# POWER.net
KiCad netlist of a schematic drawn in Altium Designer
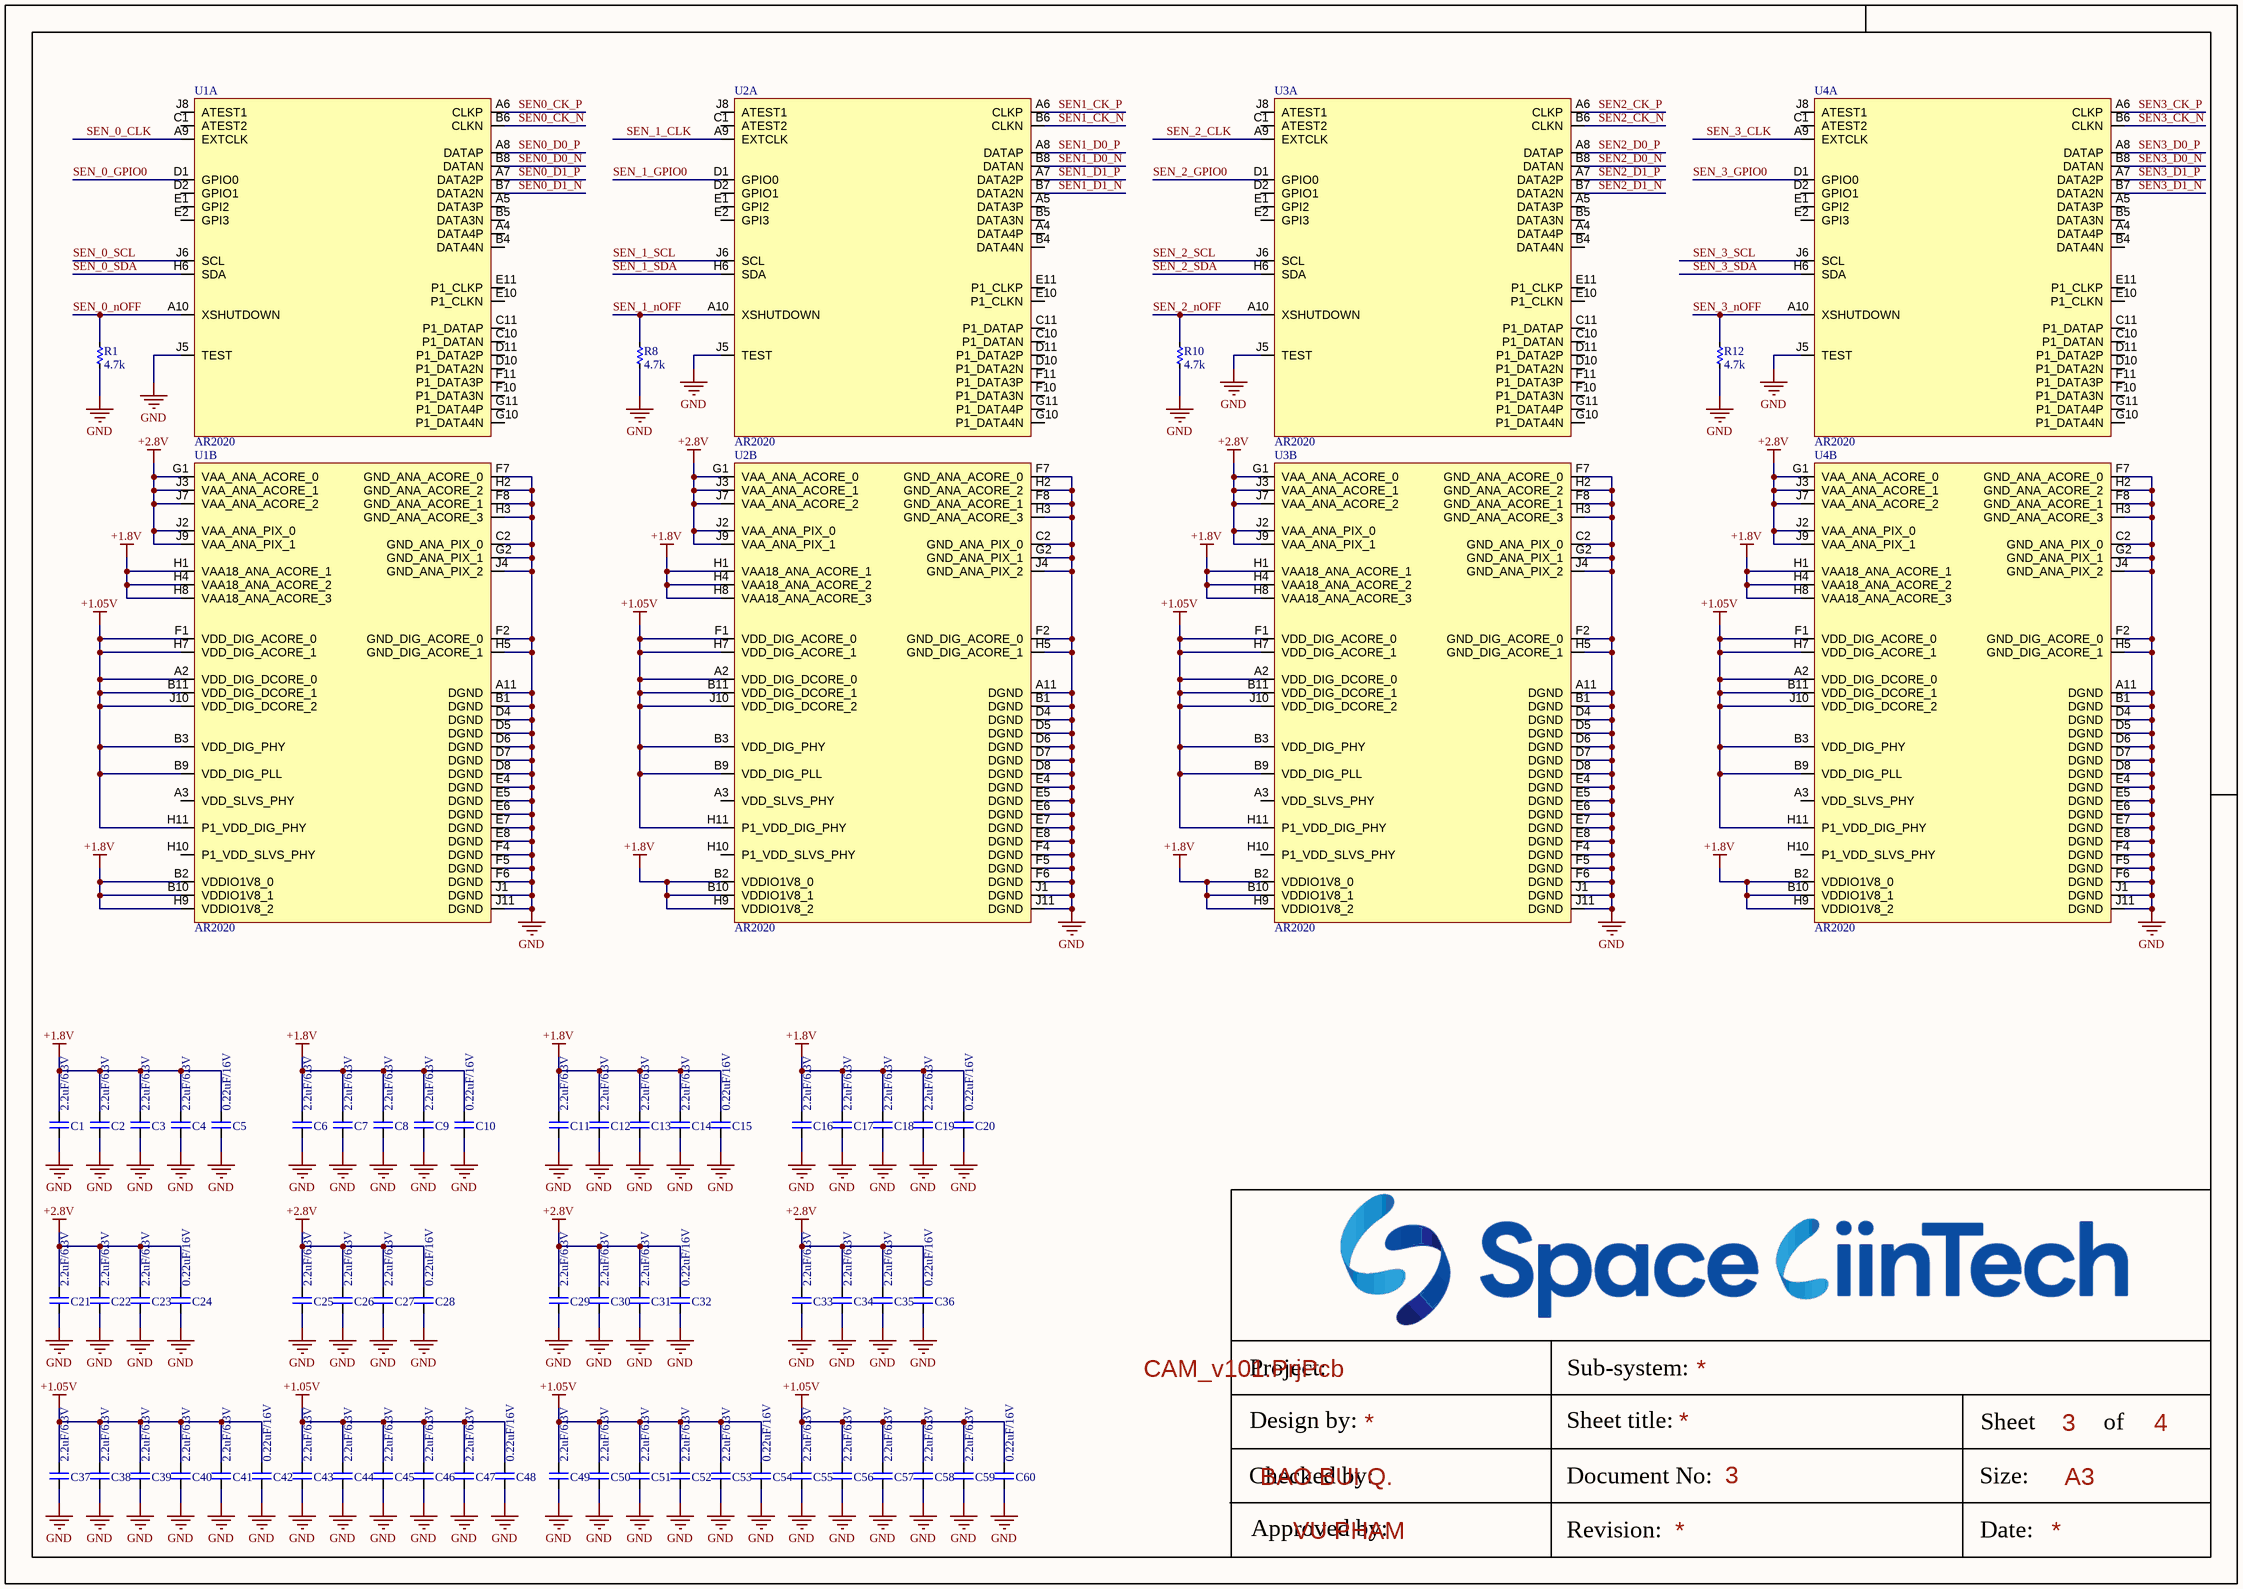
[diagram p0: POWER.SchDoc]

(export (version "E")
  (design (tool "Eeschema 10.0.6"))
  (components
    (comp (ref "C1")
      (value "2.2uF/6.3V")
      (footprint "CAP_C_1005X60")
      (description "CAP_Chip")
      (libsource (lib "LABLIB") (part "CAP_SMD"))
    )
    (comp (ref "C2")
      (value "2.2uF/6.3V")
      (footprint "CAP_C_1005X60")
      (description "CAP_Chip")
      (libsource (lib "LABLIB") (part "CAP_SMD"))
    )
    (comp (ref "C3")
      (value "2.2uF/6.3V")
      (footprint "CAP_C_1005X60")
      (description "CAP_Chip")
      (libsource (lib "LABLIB") (part "CAP_SMD"))
    )
    (comp (ref "C4")
      (value "2.2uF/6.3V")
      (footprint "CAP_C_1005X60")
      (description "CAP_Chip")
      (libsource (lib "LABLIB") (part "CAP_SMD"))
    )
    (comp (ref "C5")
      (value "0.22uF/16V")
      (footprint "CAP_C_1005X60")
      (description "CAP_Chip")
      (libsource (lib "LABLIB") (part "CAP_SMD"))
    )
    (comp (ref "C6")
      (value "2.2uF/6.3V")
      (footprint "CAP_C_1005X60")
      (description "CAP_Chip")
      (libsource (lib "LABLIB") (part "CAP_SMD"))
    )
    (comp (ref "C7")
      (value "2.2uF/6.3V")
      (footprint "CAP_C_1005X60")
      (description "CAP_Chip")
      (libsource (lib "LABLIB") (part "CAP_SMD"))
    )
    (comp (ref "C8")
      (value "2.2uF/6.3V")
      (footprint "CAP_C_1005X60")
      (description "CAP_Chip")
      (libsource (lib "LABLIB") (part "CAP_SMD"))
    )
    (comp (ref "C9")
      (value "2.2uF/6.3V")
      (footprint "CAP_C_1005X60")
      (description "CAP_Chip")
      (libsource (lib "LABLIB") (part "CAP_SMD"))
    )
    (comp (ref "C10")
      (value "0.22uF/16V")
      (footprint "CAP_C_1005X60")
      (description "CAP_Chip")
      (libsource (lib "LABLIB") (part "CAP_SMD"))
    )
    (comp (ref "C11")
      (value "2.2uF/6.3V")
      (footprint "CAP_C_1005X60")
      (description "CAP_Chip")
      (libsource (lib "LABLIB") (part "CAP_SMD"))
    )
    (comp (ref "C12")
      (value "2.2uF/6.3V")
      (footprint "CAP_C_1005X60")
      (description "CAP_Chip")
      (libsource (lib "LABLIB") (part "CAP_SMD"))
    )
    (comp (ref "C13")
      (value "2.2uF/6.3V")
      (footprint "CAP_C_1005X60")
      (description "CAP_Chip")
      (libsource (lib "LABLIB") (part "CAP_SMD"))
    )
    (comp (ref "C14")
      (value "2.2uF/6.3V")
      (footprint "CAP_C_1005X60")
      (description "CAP_Chip")
      (libsource (lib "LABLIB") (part "CAP_SMD"))
    )
    (comp (ref "C15")
      (value "0.22uF/16V")
      (footprint "CAP_C_1005X60")
      (description "CAP_Chip")
      (libsource (lib "LABLIB") (part "CAP_SMD"))
    )
    (comp (ref "C16")
      (value "2.2uF/6.3V")
      (footprint "CAP_C_1005X60")
      (description "CAP_Chip")
      (libsource (lib "LABLIB") (part "CAP_SMD"))
    )
    (comp (ref "C17")
      (value "2.2uF/6.3V")
      (footprint "CAP_C_1005X60")
      (description "CAP_Chip")
      (libsource (lib "LABLIB") (part "CAP_SMD"))
    )
    (comp (ref "C18")
      (value "2.2uF/6.3V")
      (footprint "CAP_C_1005X60")
      (description "CAP_Chip")
      (libsource (lib "LABLIB") (part "CAP_SMD"))
    )
    (comp (ref "C19")
      (value "2.2uF/6.3V")
      (footprint "CAP_C_1005X60")
      (description "CAP_Chip")
      (libsource (lib "LABLIB") (part "CAP_SMD"))
    )
    (comp (ref "C20")
      (value "0.22uF/16V")
      (footprint "CAP_C_1005X60")
      (description "CAP_Chip")
      (libsource (lib "LABLIB") (part "CAP_SMD"))
    )
    (comp (ref "C21")
      (value "2.2uF/6.3V")
      (footprint "CAP_C_1005X60")
      (description "CAP_Chip")
      (libsource (lib "LABLIB") (part "CAP_SMD"))
    )
    (comp (ref "C22")
      (value "2.2uF/6.3V")
      (footprint "CAP_C_1005X60")
      (description "CAP_Chip")
      (libsource (lib "LABLIB") (part "CAP_SMD"))
    )
    (comp (ref "C23")
      (value "2.2uF/6.3V")
      (footprint "CAP_C_1005X60")
      (description "CAP_Chip")
      (libsource (lib "LABLIB") (part "CAP_SMD"))
    )
    (comp (ref "C24")
      (value "0.22uF/16V")
      (footprint "CAP_C_1005X60")
      (description "CAP_Chip")
      (libsource (lib "LABLIB") (part "CAP_SMD"))
    )
    (comp (ref "C25")
      (value "2.2uF/6.3V")
      (footprint "CAP_C_1005X60")
      (description "CAP_Chip")
      (libsource (lib "LABLIB") (part "CAP_SMD"))
    )
    (comp (ref "C26")
      (value "2.2uF/6.3V")
      (footprint "CAP_C_1005X60")
      (description "CAP_Chip")
      (libsource (lib "LABLIB") (part "CAP_SMD"))
    )
    (comp (ref "C27")
      (value "2.2uF/6.3V")
      (footprint "CAP_C_1005X60")
      (description "CAP_Chip")
      (libsource (lib "LABLIB") (part "CAP_SMD"))
    )
    (comp (ref "C28")
      (value "0.22uF/16V")
      (footprint "CAP_C_1005X60")
      (description "CAP_Chip")
      (libsource (lib "LABLIB") (part "CAP_SMD"))
    )
    (comp (ref "C29")
      (value "2.2uF/6.3V")
      (footprint "CAP_C_1005X60")
      (description "CAP_Chip")
      (libsource (lib "LABLIB") (part "CAP_SMD"))
    )
    (comp (ref "C30")
      (value "2.2uF/6.3V")
      (footprint "CAP_C_1005X60")
      (description "CAP_Chip")
      (libsource (lib "LABLIB") (part "CAP_SMD"))
    )
    (comp (ref "C31")
      (value "2.2uF/6.3V")
      (footprint "CAP_C_1005X60")
      (description "CAP_Chip")
      (libsource (lib "LABLIB") (part "CAP_SMD"))
    )
    (comp (ref "C32")
      (value "0.22uF/16V")
      (footprint "CAP_C_1005X60")
      (description "CAP_Chip")
      (libsource (lib "LABLIB") (part "CAP_SMD"))
    )
    (comp (ref "C33")
      (value "2.2uF/6.3V")
      (footprint "CAP_C_1005X60")
      (description "CAP_Chip")
      (libsource (lib "LABLIB") (part "CAP_SMD"))
    )
    (comp (ref "C34")
      (value "2.2uF/6.3V")
      (footprint "CAP_C_1005X60")
      (description "CAP_Chip")
      (libsource (lib "LABLIB") (part "CAP_SMD"))
    )
    (comp (ref "C35")
      (value "2.2uF/6.3V")
      (footprint "CAP_C_1005X60")
      (description "CAP_Chip")
      (libsource (lib "LABLIB") (part "CAP_SMD"))
    )
    (comp (ref "C36")
      (value "0.22uF/16V")
      (footprint "CAP_C_1005X60")
      (description "CAP_Chip")
      (libsource (lib "LABLIB") (part "CAP_SMD"))
    )
    (comp (ref "C37")
      (value "2.2uF/6.3V")
      (footprint "CAP_C_1005X60")
      (description "CAP_Chip")
      (libsource (lib "LABLIB") (part "CAP_SMD"))
    )
    (comp (ref "C38")
      (value "2.2uF/6.3V")
      (footprint "CAP_C_1005X60")
      (description "CAP_Chip")
      (libsource (lib "LABLIB") (part "CAP_SMD"))
    )
    (comp (ref "C39")
      (value "2.2uF/6.3V")
      (footprint "CAP_C_1005X60")
      (description "CAP_Chip")
      (libsource (lib "LABLIB") (part "CAP_SMD"))
    )
    (comp (ref "C40")
      (value "2.2uF/6.3V")
      (footprint "CAP_C_1005X60")
      (description "CAP_Chip")
      (libsource (lib "LABLIB") (part "CAP_SMD"))
    )
    (comp (ref "C41")
      (value "2.2uF/6.3V")
      (footprint "CAP_C_1005X60")
      (description "CAP_Chip")
      (libsource (lib "LABLIB") (part "CAP_SMD"))
    )
    (comp (ref "C42")
      (value "0.22uF/16V")
      (footprint "CAP_C_1005X60")
      (description "CAP_Chip")
      (libsource (lib "LABLIB") (part "CAP_SMD"))
    )
    (comp (ref "C43")
      (value "2.2uF/6.3V")
      (footprint "CAP_C_1005X60")
      (description "CAP_Chip")
      (libsource (lib "LABLIB") (part "CAP_SMD"))
    )
    (comp (ref "C44")
      (value "2.2uF/6.3V")
      (footprint "CAP_C_1005X60")
      (description "CAP_Chip")
      (libsource (lib "LABLIB") (part "CAP_SMD"))
    )
    (comp (ref "C45")
      (value "2.2uF/6.3V")
      (footprint "CAP_C_1005X60")
      (description "CAP_Chip")
      (libsource (lib "LABLIB") (part "CAP_SMD"))
    )
    (comp (ref "C46")
      (value "2.2uF/6.3V")
      (footprint "CAP_C_1005X60")
      (description "CAP_Chip")
      (libsource (lib "LABLIB") (part "CAP_SMD"))
    )
    (comp (ref "C47")
      (value "2.2uF/6.3V")
      (footprint "CAP_C_1005X60")
      (description "CAP_Chip")
      (libsource (lib "LABLIB") (part "CAP_SMD"))
    )
    (comp (ref "C48")
      (value "0.22uF/16V")
      (footprint "CAP_C_1005X60")
      (description "CAP_Chip")
      (libsource (lib "LABLIB") (part "CAP_SMD"))
    )
    (comp (ref "C49")
      (value "2.2uF/6.3V")
      (footprint "CAP_C_1005X60")
      (description "CAP_Chip")
      (libsource (lib "LABLIB") (part "CAP_SMD"))
    )
    (comp (ref "C50")
      (value "2.2uF/6.3V")
      (footprint "CAP_C_1005X60")
      (description "CAP_Chip")
      (libsource (lib "LABLIB") (part "CAP_SMD"))
    )
    (comp (ref "C51")
      (value "2.2uF/6.3V")
      (footprint "CAP_C_1005X60")
      (description "CAP_Chip")
      (libsource (lib "LABLIB") (part "CAP_SMD"))
    )
    (comp (ref "C52")
      (value "2.2uF/6.3V")
      (footprint "CAP_C_1005X60")
      (description "CAP_Chip")
      (libsource (lib "LABLIB") (part "CAP_SMD"))
    )
    (comp (ref "C53")
      (value "2.2uF/6.3V")
      (footprint "CAP_C_1005X60")
      (description "CAP_Chip")
      (libsource (lib "LABLIB") (part "CAP_SMD"))
    )
    (comp (ref "C54")
      (value "0.22uF/16V")
      (footprint "CAP_C_1005X60")
      (description "CAP_Chip")
      (libsource (lib "LABLIB") (part "CAP_SMD"))
    )
    (comp (ref "C55")
      (value "2.2uF/6.3V")
      (footprint "CAP_C_1005X60")
      (description "CAP_Chip")
      (libsource (lib "LABLIB") (part "CAP_SMD"))
    )
    (comp (ref "C56")
      (value "2.2uF/6.3V")
      (footprint "CAP_C_1005X60")
      (description "CAP_Chip")
      (libsource (lib "LABLIB") (part "CAP_SMD"))
    )
    (comp (ref "C57")
      (value "2.2uF/6.3V")
      (footprint "CAP_C_1005X60")
      (description "CAP_Chip")
      (libsource (lib "LABLIB") (part "CAP_SMD"))
    )
    (comp (ref "C58")
      (value "2.2uF/6.3V")
      (footprint "CAP_C_1005X60")
      (description "CAP_Chip")
      (libsource (lib "LABLIB") (part "CAP_SMD"))
    )
    (comp (ref "C59")
      (value "2.2uF/6.3V")
      (footprint "CAP_C_1005X60")
      (description "CAP_Chip")
      (libsource (lib "LABLIB") (part "CAP_SMD"))
    )
    (comp (ref "C60")
      (value "0.22uF/16V")
      (footprint "CAP_C_1005X60")
      (description "CAP_Chip")
      (libsource (lib "LABLIB") (part "CAP_SMD"))
    )
    (comp (ref "R1")
      (value "4.7k")
      (footprint "RES_C_1005X40")
      (description "RES-Chip")
      (fields
        (field (name "MANUFACTURER") "Generic Components")
        (field (name "PUBLISHER") "Altium Hobart Technology Centre")
      )
      (libsource (lib "LABLIB") (part "RES-SMD"))
    )
    (comp (ref "R8")
      (value "4.7k")
      (footprint "RES_C_1005X40")
      (description "RES-Chip")
      (fields
        (field (name "MANUFACTURER") "Generic Components")
        (field (name "PUBLISHER") "Altium Hobart Technology Centre")
      )
      (libsource (lib "LABLIB") (part "RES-SMD"))
    )
    (comp (ref "R10")
      (value "4.7k")
      (footprint "RES_C_1005X40")
      (description "RES-Chip")
      (fields
        (field (name "MANUFACTURER") "Generic Components")
        (field (name "PUBLISHER") "Altium Hobart Technology Centre")
      )
      (libsource (lib "LABLIB") (part "RES-SMD"))
    )
    (comp (ref "R12")
      (value "4.7k")
      (footprint "RES_C_1005X40")
      (description "RES-Chip")
      (fields
        (field (name "MANUFACTURER") "Generic Components")
        (field (name "PUBLISHER") "Altium Hobart Technology Centre")
      )
      (libsource (lib "LABLIB") (part "RES-SMD"))
    )
    (comp (ref "U1")
      (value "AR2020")
      (footprint "BGA78C100P11X9_1300X1050X210")
      (libsource (lib "CAMERA_SchLib") (part "AR2020"))
    )
    (comp (ref "U2")
      (value "AR2020")
      (footprint "BGA78C100P11X9_1300X1050X210")
      (libsource (lib "CAMERA_SchLib") (part "AR2020"))
    )
    (comp (ref "U3")
      (value "AR2020")
      (footprint "BGA78C100P11X9_1300X1050X210")
      (libsource (lib "CAMERA_SchLib") (part "AR2020"))
    )
    (comp (ref "U4")
      (value "AR2020")
      (footprint "BGA78C100P11X9_1300X1050X210")
      (libsource (lib "CAMERA_SchLib") (part "AR2020"))
    )
  )
  (nets
    (net (code "1") (name "+1.05V") (class "Default")
      (node (ref "C37") (pin "2") (pinfunction "2_2") (pintype "passive"))
      (node (ref "C38") (pin "2") (pinfunction "2_2") (pintype "passive"))
      (node (ref "C39") (pin "2") (pinfunction "2_2") (pintype "passive"))
      (node (ref "C40") (pin "2") (pinfunction "2_2") (pintype "passive"))
      (node (ref "C41") (pin "2") (pinfunction "2_2") (pintype "passive"))
      (node (ref "C42") (pin "2") (pinfunction "2_2") (pintype "passive"))
      (node (ref "C43") (pin "2") (pinfunction "2_2") (pintype "passive"))
      (node (ref "C44") (pin "2") (pinfunction "2_2") (pintype "passive"))
      (node (ref "C45") (pin "2") (pinfunction "2_2") (pintype "passive"))
      (node (ref "C46") (pin "2") (pinfunction "2_2") (pintype "passive"))
      (node (ref "C47") (pin "2") (pinfunction "2_2") (pintype "passive"))
      (node (ref "C48") (pin "2") (pinfunction "2_2") (pintype "passive"))
      (node (ref "C49") (pin "2") (pinfunction "2_2") (pintype "passive"))
      (node (ref "C50") (pin "2") (pinfunction "2_2") (pintype "passive"))
      (node (ref "C51") (pin "2") (pinfunction "2_2") (pintype "passive"))
      (node (ref "C52") (pin "2") (pinfunction "2_2") (pintype "passive"))
      (node (ref "C53") (pin "2") (pinfunction "2_2") (pintype "passive"))
      (node (ref "C54") (pin "2") (pinfunction "2_2") (pintype "passive"))
      (node (ref "C55") (pin "2") (pinfunction "2_2") (pintype "passive"))
      (node (ref "C56") (pin "2") (pinfunction "2_2") (pintype "passive"))
      (node (ref "C57") (pin "2") (pinfunction "2_2") (pintype "passive"))
      (node (ref "C58") (pin "2") (pinfunction "2_2") (pintype "passive"))
      (node (ref "C59") (pin "2") (pinfunction "2_2") (pintype "passive"))
      (node (ref "C60") (pin "2") (pinfunction "2_2") (pintype "passive"))
      (node (ref "U1") (pin "A2") (pinfunction "VDD_DIG_DCORE_0_A2") (pintype "passive"))
      (node (ref "U1") (pin "B11") (pinfunction "VDD_DIG_DCORE_1_B11") (pintype "passive"))
      (node (ref "U1") (pin "B3") (pinfunction "VDD_DIG_PHY_B3") (pintype "passive"))
      (node (ref "U1") (pin "B9") (pinfunction "VDD_DIG_PLL_B9") (pintype "passive"))
      (node (ref "U1") (pin "F1") (pinfunction "VDD_DIG_ACORE_0_F1") (pintype "passive"))
      (node (ref "U1") (pin "H11") (pinfunction "P1_VDD_DIG_PHY_H11") (pintype "passive"))
      (node (ref "U1") (pin "H7") (pinfunction "VDD_DIG_ACORE_1_H7") (pintype "passive"))
      (node (ref "U1") (pin "J10") (pinfunction "VDD_DIG_DCORE_2_J10") (pintype "passive"))
      (node (ref "U2") (pin "A2") (pinfunction "VDD_DIG_DCORE_0_A2") (pintype "passive"))
      (node (ref "U2") (pin "B11") (pinfunction "VDD_DIG_DCORE_1_B11") (pintype "passive"))
      (node (ref "U2") (pin "B3") (pinfunction "VDD_DIG_PHY_B3") (pintype "passive"))
      (node (ref "U2") (pin "B9") (pinfunction "VDD_DIG_PLL_B9") (pintype "passive"))
      (node (ref "U2") (pin "F1") (pinfunction "VDD_DIG_ACORE_0_F1") (pintype "passive"))
      (node (ref "U2") (pin "H11") (pinfunction "P1_VDD_DIG_PHY_H11") (pintype "passive"))
      (node (ref "U2") (pin "H7") (pinfunction "VDD_DIG_ACORE_1_H7") (pintype "passive"))
      (node (ref "U2") (pin "J10") (pinfunction "VDD_DIG_DCORE_2_J10") (pintype "passive"))
      (node (ref "U3") (pin "A2") (pinfunction "VDD_DIG_DCORE_0_A2") (pintype "passive"))
      (node (ref "U3") (pin "B11") (pinfunction "VDD_DIG_DCORE_1_B11") (pintype "passive"))
      (node (ref "U3") (pin "B3") (pinfunction "VDD_DIG_PHY_B3") (pintype "passive"))
      (node (ref "U3") (pin "B9") (pinfunction "VDD_DIG_PLL_B9") (pintype "passive"))
      (node (ref "U3") (pin "F1") (pinfunction "VDD_DIG_ACORE_0_F1") (pintype "passive"))
      (node (ref "U3") (pin "H11") (pinfunction "P1_VDD_DIG_PHY_H11") (pintype "passive"))
      (node (ref "U3") (pin "H7") (pinfunction "VDD_DIG_ACORE_1_H7") (pintype "passive"))
      (node (ref "U3") (pin "J10") (pinfunction "VDD_DIG_DCORE_2_J10") (pintype "passive"))
      (node (ref "U4") (pin "A2") (pinfunction "VDD_DIG_DCORE_0_A2") (pintype "passive"))
      (node (ref "U4") (pin "B11") (pinfunction "VDD_DIG_DCORE_1_B11") (pintype "passive"))
      (node (ref "U4") (pin "B3") (pinfunction "VDD_DIG_PHY_B3") (pintype "passive"))
      (node (ref "U4") (pin "B9") (pinfunction "VDD_DIG_PLL_B9") (pintype "passive"))
      (node (ref "U4") (pin "F1") (pinfunction "VDD_DIG_ACORE_0_F1") (pintype "passive"))
      (node (ref "U4") (pin "H11") (pinfunction "P1_VDD_DIG_PHY_H11") (pintype "passive"))
      (node (ref "U4") (pin "H7") (pinfunction "VDD_DIG_ACORE_1_H7") (pintype "passive"))
      (node (ref "U4") (pin "J10") (pinfunction "VDD_DIG_DCORE_2_J10") (pintype "passive"))
    )
    (net (code "2") (name "+1.8V") (class "Default")
      (node (ref "C1") (pin "2") (pinfunction "2_2") (pintype "passive"))
      (node (ref "C10") (pin "2") (pinfunction "2_2") (pintype "passive"))
      (node (ref "C11") (pin "2") (pinfunction "2_2") (pintype "passive"))
      (node (ref "C12") (pin "2") (pinfunction "2_2") (pintype "passive"))
      (node (ref "C13") (pin "2") (pinfunction "2_2") (pintype "passive"))
      (node (ref "C14") (pin "2") (pinfunction "2_2") (pintype "passive"))
      (node (ref "C15") (pin "2") (pinfunction "2_2") (pintype "passive"))
      (node (ref "C16") (pin "2") (pinfunction "2_2") (pintype "passive"))
      (node (ref "C17") (pin "2") (pinfunction "2_2") (pintype "passive"))
      (node (ref "C18") (pin "2") (pinfunction "2_2") (pintype "passive"))
      (node (ref "C19") (pin "2") (pinfunction "2_2") (pintype "passive"))
      (node (ref "C2") (pin "2") (pinfunction "2_2") (pintype "passive"))
      (node (ref "C20") (pin "2") (pinfunction "2_2") (pintype "passive"))
      (node (ref "C3") (pin "2") (pinfunction "2_2") (pintype "passive"))
      (node (ref "C4") (pin "2") (pinfunction "2_2") (pintype "passive"))
      (node (ref "C5") (pin "2") (pinfunction "2_2") (pintype "passive"))
      (node (ref "C6") (pin "2") (pinfunction "2_2") (pintype "passive"))
      (node (ref "C7") (pin "2") (pinfunction "2_2") (pintype "passive"))
      (node (ref "C8") (pin "2") (pinfunction "2_2") (pintype "passive"))
      (node (ref "C9") (pin "2") (pinfunction "2_2") (pintype "passive"))
      (node (ref "U1") (pin "B10") (pinfunction "VDDIO1V8_1_B10") (pintype "passive"))
      (node (ref "U1") (pin "B2") (pinfunction "VDDIO1V8_0_B2") (pintype "passive"))
      (node (ref "U1") (pin "H1") (pinfunction "VAA18_ANA_ACORE_1_H1") (pintype "passive"))
      (node (ref "U1") (pin "H4") (pinfunction "VAA18_ANA_ACORE_2_H4") (pintype "passive"))
      (node (ref "U1") (pin "H8") (pinfunction "VAA18_ANA_ACORE_3_H8") (pintype "passive"))
      (node (ref "U1") (pin "H9") (pinfunction "VDDIO1V8_2_H9") (pintype "passive"))
      (node (ref "U2") (pin "B10") (pinfunction "VDDIO1V8_1_B10") (pintype "passive"))
      (node (ref "U2") (pin "B2") (pinfunction "VDDIO1V8_0_B2") (pintype "passive"))
      (node (ref "U2") (pin "H1") (pinfunction "VAA18_ANA_ACORE_1_H1") (pintype "passive"))
      (node (ref "U2") (pin "H4") (pinfunction "VAA18_ANA_ACORE_2_H4") (pintype "passive"))
      (node (ref "U2") (pin "H8") (pinfunction "VAA18_ANA_ACORE_3_H8") (pintype "passive"))
      (node (ref "U2") (pin "H9") (pinfunction "VDDIO1V8_2_H9") (pintype "passive"))
      (node (ref "U3") (pin "B10") (pinfunction "VDDIO1V8_1_B10") (pintype "passive"))
      (node (ref "U3") (pin "B2") (pinfunction "VDDIO1V8_0_B2") (pintype "passive"))
      (node (ref "U3") (pin "H1") (pinfunction "VAA18_ANA_ACORE_1_H1") (pintype "passive"))
      (node (ref "U3") (pin "H4") (pinfunction "VAA18_ANA_ACORE_2_H4") (pintype "passive"))
      (node (ref "U3") (pin "H8") (pinfunction "VAA18_ANA_ACORE_3_H8") (pintype "passive"))
      (node (ref "U3") (pin "H9") (pinfunction "VDDIO1V8_2_H9") (pintype "passive"))
      (node (ref "U4") (pin "B10") (pinfunction "VDDIO1V8_1_B10") (pintype "passive"))
      (node (ref "U4") (pin "B2") (pinfunction "VDDIO1V8_0_B2") (pintype "passive"))
      (node (ref "U4") (pin "H1") (pinfunction "VAA18_ANA_ACORE_1_H1") (pintype "passive"))
      (node (ref "U4") (pin "H4") (pinfunction "VAA18_ANA_ACORE_2_H4") (pintype "passive"))
      (node (ref "U4") (pin "H8") (pinfunction "VAA18_ANA_ACORE_3_H8") (pintype "passive"))
      (node (ref "U4") (pin "H9") (pinfunction "VDDIO1V8_2_H9") (pintype "passive"))
    )
    (net (code "3") (name "+2.8V") (class "Default")
      (node (ref "C21") (pin "2") (pinfunction "2_2") (pintype "passive"))
      (node (ref "C22") (pin "2") (pinfunction "2_2") (pintype "passive"))
      (node (ref "C23") (pin "2") (pinfunction "2_2") (pintype "passive"))
      (node (ref "C24") (pin "2") (pinfunction "2_2") (pintype "passive"))
      (node (ref "C25") (pin "2") (pinfunction "2_2") (pintype "passive"))
      (node (ref "C26") (pin "2") (pinfunction "2_2") (pintype "passive"))
      (node (ref "C27") (pin "2") (pinfunction "2_2") (pintype "passive"))
      (node (ref "C28") (pin "2") (pinfunction "2_2") (pintype "passive"))
      (node (ref "C29") (pin "2") (pinfunction "2_2") (pintype "passive"))
      (node (ref "C30") (pin "2") (pinfunction "2_2") (pintype "passive"))
      (node (ref "C31") (pin "2") (pinfunction "2_2") (pintype "passive"))
      (node (ref "C32") (pin "2") (pinfunction "2_2") (pintype "passive"))
      (node (ref "C33") (pin "2") (pinfunction "2_2") (pintype "passive"))
      (node (ref "C34") (pin "2") (pinfunction "2_2") (pintype "passive"))
      (node (ref "C35") (pin "2") (pinfunction "2_2") (pintype "passive"))
      (node (ref "C36") (pin "2") (pinfunction "2_2") (pintype "passive"))
      (node (ref "U1") (pin "G1") (pinfunction "VAA_ANA_ACORE_0_G1") (pintype "passive"))
      (node (ref "U1") (pin "J2") (pinfunction "VAA_ANA_PIX_0_J2") (pintype "passive"))
      (node (ref "U1") (pin "J3") (pinfunction "VAA_ANA_ACORE_1_J3") (pintype "passive"))
      (node (ref "U1") (pin "J7") (pinfunction "VAA_ANA_ACORE_2_J7") (pintype "passive"))
      (node (ref "U1") (pin "J9") (pinfunction "VAA_ANA_PIX_1_J9") (pintype "passive"))
      (node (ref "U2") (pin "G1") (pinfunction "VAA_ANA_ACORE_0_G1") (pintype "passive"))
      (node (ref "U2") (pin "J2") (pinfunction "VAA_ANA_PIX_0_J2") (pintype "passive"))
      (node (ref "U2") (pin "J3") (pinfunction "VAA_ANA_ACORE_1_J3") (pintype "passive"))
      (node (ref "U2") (pin "J7") (pinfunction "VAA_ANA_ACORE_2_J7") (pintype "passive"))
      (node (ref "U2") (pin "J9") (pinfunction "VAA_ANA_PIX_1_J9") (pintype "passive"))
      (node (ref "U3") (pin "G1") (pinfunction "VAA_ANA_ACORE_0_G1") (pintype "passive"))
      (node (ref "U3") (pin "J2") (pinfunction "VAA_ANA_PIX_0_J2") (pintype "passive"))
      (node (ref "U3") (pin "J3") (pinfunction "VAA_ANA_ACORE_1_J3") (pintype "passive"))
      (node (ref "U3") (pin "J7") (pinfunction "VAA_ANA_ACORE_2_J7") (pintype "passive"))
      (node (ref "U3") (pin "J9") (pinfunction "VAA_ANA_PIX_1_J9") (pintype "passive"))
      (node (ref "U4") (pin "G1") (pinfunction "VAA_ANA_ACORE_0_G1") (pintype "passive"))
      (node (ref "U4") (pin "J2") (pinfunction "VAA_ANA_PIX_0_J2") (pintype "passive"))
      (node (ref "U4") (pin "J3") (pinfunction "VAA_ANA_ACORE_1_J3") (pintype "passive"))
      (node (ref "U4") (pin "J7") (pinfunction "VAA_ANA_ACORE_2_J7") (pintype "passive"))
      (node (ref "U4") (pin "J9") (pinfunction "VAA_ANA_PIX_1_J9") (pintype "passive"))
    )
    (net (code "4") (name "/SEN0_CK_N") (class "Default")
      (node (ref "U1") (pin "B6") (pinfunction "CLKN_B6") (pintype "passive"))
    )
    (net (code "5") (name "/SEN0_CK_P") (class "Default")
      (node (ref "U1") (pin "A6") (pinfunction "CLKP_A6") (pintype "passive"))
    )
    (net (code "6") (name "/SEN0_D0_N") (class "Default")
      (node (ref "U1") (pin "B8") (pinfunction "DATAN_B8") (pintype "passive"))
    )
    (net (code "7") (name "/SEN0_D0_P") (class "Default")
      (node (ref "U1") (pin "A8") (pinfunction "DATAP_A8") (pintype "passive"))
    )
    (net (code "8") (name "/SEN0_D1_N") (class "Default")
      (node (ref "U1") (pin "B7") (pinfunction "DATA2N_B7") (pintype "passive"))
    )
    (net (code "9") (name "/SEN0_D1_P") (class "Default")
      (node (ref "U1") (pin "A7") (pinfunction "DATA2P_A7") (pintype "passive"))
    )
    (net (code "10") (name "/SEN1_CK_N") (class "Default")
      (node (ref "U2") (pin "B6") (pinfunction "CLKN_B6") (pintype "passive"))
    )
    (net (code "11") (name "/SEN1_CK_P") (class "Default")
      (node (ref "U2") (pin "A6") (pinfunction "CLKP_A6") (pintype "passive"))
    )
    (net (code "12") (name "/SEN1_D0_N") (class "Default")
      (node (ref "U2") (pin "B8") (pinfunction "DATAN_B8") (pintype "passive"))
    )
    (net (code "13") (name "/SEN1_D0_P") (class "Default")
      (node (ref "U2") (pin "A8") (pinfunction "DATAP_A8") (pintype "passive"))
    )
    (net (code "14") (name "/SEN1_D1_N") (class "Default")
      (node (ref "U2") (pin "B7") (pinfunction "DATA2N_B7") (pintype "passive"))
    )
    (net (code "15") (name "/SEN1_D1_P") (class "Default")
      (node (ref "U2") (pin "A7") (pinfunction "DATA2P_A7") (pintype "passive"))
    )
    (net (code "16") (name "/SEN2_CK_N") (class "Default")
      (node (ref "U3") (pin "B6") (pinfunction "CLKN_B6") (pintype "passive"))
    )
    (net (code "17") (name "/SEN2_CK_P") (class "Default")
      (node (ref "U3") (pin "A6") (pinfunction "CLKP_A6") (pintype "passive"))
    )
    (net (code "18") (name "/SEN2_D0_N") (class "Default")
      (node (ref "U3") (pin "B8") (pinfunction "DATAN_B8") (pintype "passive"))
    )
    (net (code "19") (name "/SEN2_D0_P") (class "Default")
      (node (ref "U3") (pin "A8") (pinfunction "DATAP_A8") (pintype "passive"))
    )
    (net (code "20") (name "/SEN2_D1_N") (class "Default")
      (node (ref "U3") (pin "B7") (pinfunction "DATA2N_B7") (pintype "passive"))
    )
    (net (code "21") (name "/SEN2_D1_P") (class "Default")
      (node (ref "U3") (pin "A7") (pinfunction "DATA2P_A7") (pintype "passive"))
    )
    (net (code "22") (name "/SEN3_CK_N") (class "Default")
      (node (ref "U4") (pin "B6") (pinfunction "CLKN_B6") (pintype "passive"))
    )
    (net (code "23") (name "/SEN3_CK_P") (class "Default")
      (node (ref "U4") (pin "A6") (pinfunction "CLKP_A6") (pintype "passive"))
    )
    (net (code "24") (name "/SEN3_D0_N") (class "Default")
      (node (ref "U4") (pin "B8") (pinfunction "DATAN_B8") (pintype "passive"))
    )
    (net (code "25") (name "/SEN3_D0_P") (class "Default")
      (node (ref "U4") (pin "A8") (pinfunction "DATAP_A8") (pintype "passive"))
    )
    (net (code "26") (name "/SEN3_D1_N") (class "Default")
      (node (ref "U4") (pin "B7") (pinfunction "DATA2N_B7") (pintype "passive"))
    )
    (net (code "27") (name "/SEN3_D1_P") (class "Default")
      (node (ref "U4") (pin "A7") (pinfunction "DATA2P_A7") (pintype "passive"))
    )
    (net (code "28") (name "/SEN_0_CLK") (class "Default")
      (node (ref "U1") (pin "A9") (pinfunction "EXTCLK_A9") (pintype "passive"))
    )
    (net (code "29") (name "/SEN_0_GPIO0") (class "Default")
      (node (ref "U1") (pin "D1") (pinfunction "GPIO0_D1") (pintype "passive"))
    )
    (net (code "30") (name "/SEN_0_SCL") (class "Default")
      (node (ref "U1") (pin "J6") (pinfunction "SCL_J6") (pintype "passive"))
    )
    (net (code "31") (name "/SEN_0_SDA") (class "Default")
      (node (ref "U1") (pin "H6") (pinfunction "SDA_H6") (pintype "passive"))
    )
    (net (code "32") (name "/SEN_0_nOFF") (class "Default")
      (node (ref "R1") (pin "1") (pinfunction "1_1") (pintype "passive"))
      (node (ref "U1") (pin "A10") (pinfunction "XSHUTDOWN_A10") (pintype "passive"))
    )
    (net (code "33") (name "/SEN_1_CLK") (class "Default")
      (node (ref "U2") (pin "A9") (pinfunction "EXTCLK_A9") (pintype "passive"))
    )
    (net (code "34") (name "/SEN_1_GPIO0") (class "Default")
      (node (ref "U2") (pin "D1") (pinfunction "GPIO0_D1") (pintype "passive"))
    )
    (net (code "35") (name "/SEN_1_SCL") (class "Default")
      (node (ref "U2") (pin "J6") (pinfunction "SCL_J6") (pintype "passive"))
    )
    (net (code "36") (name "/SEN_1_SDA") (class "Default")
      (node (ref "U2") (pin "H6") (pinfunction "SDA_H6") (pintype "passive"))
    )
    (net (code "37") (name "/SEN_1_nOFF") (class "Default")
      (node (ref "R8") (pin "1") (pinfunction "1_1") (pintype "passive"))
      (node (ref "U2") (pin "A10") (pinfunction "XSHUTDOWN_A10") (pintype "passive"))
    )
    (net (code "38") (name "/SEN_2_CLK") (class "Default")
      (node (ref "U3") (pin "A9") (pinfunction "EXTCLK_A9") (pintype "passive"))
    )
    (net (code "39") (name "/SEN_2_GPIO0") (class "Default")
      (node (ref "U3") (pin "D1") (pinfunction "GPIO0_D1") (pintype "passive"))
    )
    (net (code "40") (name "/SEN_2_SCL") (class "Default")
      (node (ref "U3") (pin "J6") (pinfunction "SCL_J6") (pintype "passive"))
    )
    (net (code "41") (name "/SEN_2_SDA") (class "Default")
      (node (ref "U3") (pin "H6") (pinfunction "SDA_H6") (pintype "passive"))
    )
    (net (code "42") (name "/SEN_2_nOFF") (class "Default")
      (node (ref "R10") (pin "1") (pinfunction "1_1") (pintype "passive"))
      (node (ref "U3") (pin "A10") (pinfunction "XSHUTDOWN_A10") (pintype "passive"))
    )
    (net (code "43") (name "/SEN_3_CLK") (class "Default")
      (node (ref "U4") (pin "A9") (pinfunction "EXTCLK_A9") (pintype "passive"))
    )
    (net (code "44") (name "/SEN_3_GPIO0") (class "Default")
      (node (ref "U4") (pin "D1") (pinfunction "GPIO0_D1") (pintype "passive"))
    )
    (net (code "45") (name "/SEN_3_SCL") (class "Default")
      (node (ref "U4") (pin "J6") (pinfunction "SCL_J6") (pintype "passive"))
    )
    (net (code "46") (name "/SEN_3_SDA") (class "Default")
      (node (ref "U4") (pin "H6") (pinfunction "SDA_H6") (pintype "passive"))
    )
    (net (code "47") (name "/SEN_3_nOFF") (class "Default")
      (node (ref "R12") (pin "1") (pinfunction "1_1") (pintype "passive"))
      (node (ref "U4") (pin "A10") (pinfunction "XSHUTDOWN_A10") (pintype "passive"))
    )
    (net (code "48") (name "GND") (class "Default")
      (node (ref "C1") (pin "1") (pinfunction "1_1") (pintype "passive"))
      (node (ref "C10") (pin "1") (pinfunction "1_1") (pintype "passive"))
      (node (ref "C11") (pin "1") (pinfunction "1_1") (pintype "passive"))
      (node (ref "C12") (pin "1") (pinfunction "1_1") (pintype "passive"))
      (node (ref "C13") (pin "1") (pinfunction "1_1") (pintype "passive"))
      (node (ref "C14") (pin "1") (pinfunction "1_1") (pintype "passive"))
      (node (ref "C15") (pin "1") (pinfunction "1_1") (pintype "passive"))
      (node (ref "C16") (pin "1") (pinfunction "1_1") (pintype "passive"))
      (node (ref "C17") (pin "1") (pinfunction "1_1") (pintype "passive"))
      (node (ref "C18") (pin "1") (pinfunction "1_1") (pintype "passive"))
      (node (ref "C19") (pin "1") (pinfunction "1_1") (pintype "passive"))
      (node (ref "C2") (pin "1") (pinfunction "1_1") (pintype "passive"))
      (node (ref "C20") (pin "1") (pinfunction "1_1") (pintype "passive"))
      (node (ref "C21") (pin "1") (pinfunction "1_1") (pintype "passive"))
      (node (ref "C22") (pin "1") (pinfunction "1_1") (pintype "passive"))
      (node (ref "C23") (pin "1") (pinfunction "1_1") (pintype "passive"))
      (node (ref "C24") (pin "1") (pinfunction "1_1") (pintype "passive"))
      (node (ref "C25") (pin "1") (pinfunction "1_1") (pintype "passive"))
      (node (ref "C26") (pin "1") (pinfunction "1_1") (pintype "passive"))
      (node (ref "C27") (pin "1") (pinfunction "1_1") (pintype "passive"))
      (node (ref "C28") (pin "1") (pinfunction "1_1") (pintype "passive"))
      (node (ref "C29") (pin "1") (pinfunction "1_1") (pintype "passive"))
      (node (ref "C3") (pin "1") (pinfunction "1_1") (pintype "passive"))
      (node (ref "C30") (pin "1") (pinfunction "1_1") (pintype "passive"))
      (node (ref "C31") (pin "1") (pinfunction "1_1") (pintype "passive"))
      (node (ref "C32") (pin "1") (pinfunction "1_1") (pintype "passive"))
      (node (ref "C33") (pin "1") (pinfunction "1_1") (pintype "passive"))
      (node (ref "C34") (pin "1") (pinfunction "1_1") (pintype "passive"))
      (node (ref "C35") (pin "1") (pinfunction "1_1") (pintype "passive"))
      (node (ref "C36") (pin "1") (pinfunction "1_1") (pintype "passive"))
      (node (ref "C37") (pin "1") (pinfunction "1_1") (pintype "passive"))
      (node (ref "C38") (pin "1") (pinfunction "1_1") (pintype "passive"))
      (node (ref "C39") (pin "1") (pinfunction "1_1") (pintype "passive"))
      (node (ref "C4") (pin "1") (pinfunction "1_1") (pintype "passive"))
      (node (ref "C40") (pin "1") (pinfunction "1_1") (pintype "passive"))
      (node (ref "C41") (pin "1") (pinfunction "1_1") (pintype "passive"))
      (node (ref "C42") (pin "1") (pinfunction "1_1") (pintype "passive"))
      (node (ref "C43") (pin "1") (pinfunction "1_1") (pintype "passive"))
      (node (ref "C44") (pin "1") (pinfunction "1_1") (pintype "passive"))
      (node (ref "C45") (pin "1") (pinfunction "1_1") (pintype "passive"))
      (node (ref "C46") (pin "1") (pinfunction "1_1") (pintype "passive"))
      (node (ref "C47") (pin "1") (pinfunction "1_1") (pintype "passive"))
      (node (ref "C48") (pin "1") (pinfunction "1_1") (pintype "passive"))
      (node (ref "C49") (pin "1") (pinfunction "1_1") (pintype "passive"))
      (node (ref "C5") (pin "1") (pinfunction "1_1") (pintype "passive"))
      (node (ref "C50") (pin "1") (pinfunction "1_1") (pintype "passive"))
      (node (ref "C51") (pin "1") (pinfunction "1_1") (pintype "passive"))
      (node (ref "C52") (pin "1") (pinfunction "1_1") (pintype "passive"))
      (node (ref "C53") (pin "1") (pinfunction "1_1") (pintype "passive"))
      (node (ref "C54") (pin "1") (pinfunction "1_1") (pintype "passive"))
      (node (ref "C55") (pin "1") (pinfunction "1_1") (pintype "passive"))
      (node (ref "C56") (pin "1") (pinfunction "1_1") (pintype "passive"))
      (node (ref "C57") (pin "1") (pinfunction "1_1") (pintype "passive"))
      (node (ref "C58") (pin "1") (pinfunction "1_1") (pintype "passive"))
      (node (ref "C59") (pin "1") (pinfunction "1_1") (pintype "passive"))
      (node (ref "C6") (pin "1") (pinfunction "1_1") (pintype "passive"))
      (node (ref "C60") (pin "1") (pinfunction "1_1") (pintype "passive"))
      (node (ref "C7") (pin "1") (pinfunction "1_1") (pintype "passive"))
      (node (ref "C8") (pin "1") (pinfunction "1_1") (pintype "passive"))
      (node (ref "C9") (pin "1") (pinfunction "1_1") (pintype "passive"))
      (node (ref "R1") (pin "2") (pinfunction "2_2") (pintype "passive"))
      (node (ref "R10") (pin "2") (pinfunction "2_2") (pintype "passive"))
      (node (ref "R12") (pin "2") (pinfunction "2_2") (pintype "passive"))
      (node (ref "R8") (pin "2") (pinfunction "2_2") (pintype "passive"))
      (node (ref "U1") (pin "A11") (pinfunction "DGND_A11") (pintype "passive"))
      (node (ref "U1") (pin "B1") (pinfunction "DGND_B1") (pintype "passive"))
      (node (ref "U1") (pin "C2") (pinfunction "GND_ANA_PIX_0_C2") (pintype "passive"))
      (node (ref "U1") (pin "D4") (pinfunction "DGND_D4") (pintype "passive"))
      (node (ref "U1") (pin "D5") (pinfunction "DGND_D5") (pintype "passive"))
      (node (ref "U1") (pin "D6") (pinfunction "DGND_D6") (pintype "passive"))
      (node (ref "U1") (pin "D7") (pinfunction "DGND_D7") (pintype "passive"))
      (node (ref "U1") (pin "D8") (pinfunction "DGND_D8") (pintype "passive"))
      (node (ref "U1") (pin "E4") (pinfunction "DGND_E4") (pintype "passive"))
      (node (ref "U1") (pin "E5") (pinfunction "DGND_E5") (pintype "passive"))
      (node (ref "U1") (pin "E6") (pinfunction "DGND_E6") (pintype "passive"))
      (node (ref "U1") (pin "E7") (pinfunction "DGND_E7") (pintype "passive"))
      (node (ref "U1") (pin "E8") (pinfunction "DGND_E8") (pintype "passive"))
      (node (ref "U1") (pin "F2") (pinfunction "GND_DIG_ACORE_0_F2") (pintype "passive"))
      (node (ref "U1") (pin "F4") (pinfunction "DGND_F4") (pintype "passive"))
      (node (ref "U1") (pin "F5") (pinfunction "DGND_F5") (pintype "passive"))
      (node (ref "U1") (pin "F6") (pinfunction "DGND_F6") (pintype "passive"))
      (node (ref "U1") (pin "F7") (pinfunction "GND_ANA_ACORE_0_F7") (pintype "passive"))
      (node (ref "U1") (pin "F8") (pinfunction "GND_ANA_ACORE_1_F8") (pintype "passive"))
      (node (ref "U1") (pin "G2") (pinfunction "GND_ANA_PIX_1_G2") (pintype "passive"))
      (node (ref "U1") (pin "H2") (pinfunction "GND_ANA_ACORE_2_H2") (pintype "passive"))
      (node (ref "U1") (pin "H3") (pinfunction "GND_ANA_ACORE_3_H3") (pintype "passive"))
      (node (ref "U1") (pin "H5") (pinfunction "GND_DIG_ACORE_1_H5") (pintype "passive"))
      (node (ref "U1") (pin "J1") (pinfunction "DGND_J1") (pintype "passive"))
      (node (ref "U1") (pin "J11") (pinfunction "DGND_J11") (pintype "passive"))
      (node (ref "U1") (pin "J4") (pinfunction "GND_ANA_PIX_2_J4") (pintype "passive"))
      (node (ref "U1") (pin "J5") (pinfunction "TEST_J5") (pintype "passive"))
      (node (ref "U2") (pin "A11") (pinfunction "DGND_A11") (pintype "passive"))
      (node (ref "U2") (pin "B1") (pinfunction "DGND_B1") (pintype "passive"))
      (node (ref "U2") (pin "C2") (pinfunction "GND_ANA_PIX_0_C2") (pintype "passive"))
      (node (ref "U2") (pin "D4") (pinfunction "DGND_D4") (pintype "passive"))
      (node (ref "U2") (pin "D5") (pinfunction "DGND_D5") (pintype "passive"))
      (node (ref "U2") (pin "D6") (pinfunction "DGND_D6") (pintype "passive"))
      (node (ref "U2") (pin "D7") (pinfunction "DGND_D7") (pintype "passive"))
      (node (ref "U2") (pin "D8") (pinfunction "DGND_D8") (pintype "passive"))
      (node (ref "U2") (pin "E4") (pinfunction "DGND_E4") (pintype "passive"))
      (node (ref "U2") (pin "E5") (pinfunction "DGND_E5") (pintype "passive"))
      (node (ref "U2") (pin "E6") (pinfunction "DGND_E6") (pintype "passive"))
      (node (ref "U2") (pin "E7") (pinfunction "DGND_E7") (pintype "passive"))
      (node (ref "U2") (pin "E8") (pinfunction "DGND_E8") (pintype "passive"))
      (node (ref "U2") (pin "F2") (pinfunction "GND_DIG_ACORE_0_F2") (pintype "passive"))
      (node (ref "U2") (pin "F4") (pinfunction "DGND_F4") (pintype "passive"))
      (node (ref "U2") (pin "F5") (pinfunction "DGND_F5") (pintype "passive"))
      (node (ref "U2") (pin "F6") (pinfunction "DGND_F6") (pintype "passive"))
      (node (ref "U2") (pin "F7") (pinfunction "GND_ANA_ACORE_0_F7") (pintype "passive"))
      (node (ref "U2") (pin "F8") (pinfunction "GND_ANA_ACORE_1_F8") (pintype "passive"))
      (node (ref "U2") (pin "G2") (pinfunction "GND_ANA_PIX_1_G2") (pintype "passive"))
      (node (ref "U2") (pin "H2") (pinfunction "GND_ANA_ACORE_2_H2") (pintype "passive"))
      (node (ref "U2") (pin "H3") (pinfunction "GND_ANA_ACORE_3_H3") (pintype "passive"))
      (node (ref "U2") (pin "H5") (pinfunction "GND_DIG_ACORE_1_H5") (pintype "passive"))
      (node (ref "U2") (pin "J1") (pinfunction "DGND_J1") (pintype "passive"))
      (node (ref "U2") (pin "J11") (pinfunction "DGND_J11") (pintype "passive"))
      (node (ref "U2") (pin "J4") (pinfunction "GND_ANA_PIX_2_J4") (pintype "passive"))
      (node (ref "U2") (pin "J5") (pinfunction "TEST_J5") (pintype "passive"))
      (node (ref "U3") (pin "A11") (pinfunction "DGND_A11") (pintype "passive"))
      (node (ref "U3") (pin "B1") (pinfunction "DGND_B1") (pintype "passive"))
      (node (ref "U3") (pin "C2") (pinfunction "GND_ANA_PIX_0_C2") (pintype "passive"))
      (node (ref "U3") (pin "D4") (pinfunction "DGND_D4") (pintype "passive"))
      (node (ref "U3") (pin "D5") (pinfunction "DGND_D5") (pintype "passive"))
      (node (ref "U3") (pin "D6") (pinfunction "DGND_D6") (pintype "passive"))
      (node (ref "U3") (pin "D7") (pinfunction "DGND_D7") (pintype "passive"))
      (node (ref "U3") (pin "D8") (pinfunction "DGND_D8") (pintype "passive"))
      (node (ref "U3") (pin "E4") (pinfunction "DGND_E4") (pintype "passive"))
      (node (ref "U3") (pin "E5") (pinfunction "DGND_E5") (pintype "passive"))
      (node (ref "U3") (pin "E6") (pinfunction "DGND_E6") (pintype "passive"))
      (node (ref "U3") (pin "E7") (pinfunction "DGND_E7") (pintype "passive"))
      (node (ref "U3") (pin "E8") (pinfunction "DGND_E8") (pintype "passive"))
      (node (ref "U3") (pin "F2") (pinfunction "GND_DIG_ACORE_0_F2") (pintype "passive"))
      (node (ref "U3") (pin "F4") (pinfunction "DGND_F4") (pintype "passive"))
      (node (ref "U3") (pin "F5") (pinfunction "DGND_F5") (pintype "passive"))
      (node (ref "U3") (pin "F6") (pinfunction "DGND_F6") (pintype "passive"))
      (node (ref "U3") (pin "F7") (pinfunction "GND_ANA_ACORE_0_F7") (pintype "passive"))
      (node (ref "U3") (pin "F8") (pinfunction "GND_ANA_ACORE_1_F8") (pintype "passive"))
      (node (ref "U3") (pin "G2") (pinfunction "GND_ANA_PIX_1_G2") (pintype "passive"))
      (node (ref "U3") (pin "H2") (pinfunction "GND_ANA_ACORE_2_H2") (pintype "passive"))
      (node (ref "U3") (pin "H3") (pinfunction "GND_ANA_ACORE_3_H3") (pintype "passive"))
      (node (ref "U3") (pin "H5") (pinfunction "GND_DIG_ACORE_1_H5") (pintype "passive"))
      (node (ref "U3") (pin "J1") (pinfunction "DGND_J1") (pintype "passive"))
      (node (ref "U3") (pin "J11") (pinfunction "DGND_J11") (pintype "passive"))
      (node (ref "U3") (pin "J4") (pinfunction "GND_ANA_PIX_2_J4") (pintype "passive"))
      (node (ref "U3") (pin "J5") (pinfunction "TEST_J5") (pintype "passive"))
      (node (ref "U4") (pin "A11") (pinfunction "DGND_A11") (pintype "passive"))
      (node (ref "U4") (pin "B1") (pinfunction "DGND_B1") (pintype "passive"))
      (node (ref "U4") (pin "C2") (pinfunction "GND_ANA_PIX_0_C2") (pintype "passive"))
      (node (ref "U4") (pin "D4") (pinfunction "DGND_D4") (pintype "passive"))
      (node (ref "U4") (pin "D5") (pinfunction "DGND_D5") (pintype "passive"))
      (node (ref "U4") (pin "D6") (pinfunction "DGND_D6") (pintype "passive"))
      (node (ref "U4") (pin "D7") (pinfunction "DGND_D7") (pintype "passive"))
      (node (ref "U4") (pin "D8") (pinfunction "DGND_D8") (pintype "passive"))
      (node (ref "U4") (pin "E4") (pinfunction "DGND_E4") (pintype "passive"))
      (node (ref "U4") (pin "E5") (pinfunction "DGND_E5") (pintype "passive"))
      (node (ref "U4") (pin "E6") (pinfunction "DGND_E6") (pintype "passive"))
      (node (ref "U4") (pin "E7") (pinfunction "DGND_E7") (pintype "passive"))
      (node (ref "U4") (pin "E8") (pinfunction "DGND_E8") (pintype "passive"))
      (node (ref "U4") (pin "F2") (pinfunction "GND_DIG_ACORE_0_F2") (pintype "passive"))
      (node (ref "U4") (pin "F4") (pinfunction "DGND_F4") (pintype "passive"))
      (node (ref "U4") (pin "F5") (pinfunction "DGND_F5") (pintype "passive"))
      (node (ref "U4") (pin "F6") (pinfunction "DGND_F6") (pintype "passive"))
      (node (ref "U4") (pin "F7") (pinfunction "GND_ANA_ACORE_0_F7") (pintype "passive"))
      (node (ref "U4") (pin "F8") (pinfunction "GND_ANA_ACORE_1_F8") (pintype "passive"))
      (node (ref "U4") (pin "G2") (pinfunction "GND_ANA_PIX_1_G2") (pintype "passive"))
      (node (ref "U4") (pin "H2") (pinfunction "GND_ANA_ACORE_2_H2") (pintype "passive"))
      (node (ref "U4") (pin "H3") (pinfunction "GND_ANA_ACORE_3_H3") (pintype "passive"))
      (node (ref "U4") (pin "H5") (pinfunction "GND_DIG_ACORE_1_H5") (pintype "passive"))
      (node (ref "U4") (pin "J1") (pinfunction "DGND_J1") (pintype "passive"))
      (node (ref "U4") (pin "J11") (pinfunction "DGND_J11") (pintype "passive"))
      (node (ref "U4") (pin "J4") (pinfunction "GND_ANA_PIX_2_J4") (pintype "passive"))
      (node (ref "U4") (pin "J5") (pinfunction "TEST_J5") (pintype "passive"))
    )
    (net (code "49") (name "unconnected-(U1A-ATEST1-PadJ8)") (class "Default")
      (node (ref "U1") (pin "J8") (pinfunction "ATEST1_J8") (pintype "passive"))
    )
    (net (code "50") (name "unconnected-(U1A-ATEST2-PadC1)") (class "Default")
      (node (ref "U1") (pin "C1") (pinfunction "ATEST2_C1") (pintype "passive"))
    )
    (net (code "51") (name "unconnected-(U1A-DATA3N-PadB5)") (class "Default")
      (node (ref "U1") (pin "B5") (pinfunction "DATA3N_B5") (pintype "passive"))
    )
    (net (code "52") (name "unconnected-(U1A-DATA3P-PadA5)") (class "Default")
      (node (ref "U1") (pin "A5") (pinfunction "DATA3P_A5") (pintype "passive"))
    )
    (net (code "53") (name "unconnected-(U1A-DATA4N-PadB4)") (class "Default")
      (node (ref "U1") (pin "B4") (pinfunction "DATA4N_B4") (pintype "passive"))
    )
    (net (code "54") (name "unconnected-(U1A-DATA4P-PadA4)") (class "Default")
      (node (ref "U1") (pin "A4") (pinfunction "DATA4P_A4") (pintype "passive"))
    )
    (net (code "55") (name "unconnected-(U1A-GPI2-PadE1)") (class "Default")
      (node (ref "U1") (pin "E1") (pinfunction "GPI2_E1") (pintype "passive"))
    )
    (net (code "56") (name "unconnected-(U1A-GPI3-PadE2)") (class "Default")
      (node (ref "U1") (pin "E2") (pinfunction "GPI3_E2") (pintype "passive"))
    )
    (net (code "57") (name "unconnected-(U1A-GPIO1-PadD2)") (class "Default")
      (node (ref "U1") (pin "D2") (pinfunction "GPIO1_D2") (pintype "passive"))
    )
    (net (code "58") (name "unconnected-(U1A-P1_CLKN-PadE10)") (class "Default")
      (node (ref "U1") (pin "E10") (pinfunction "P1_CLKN_E10") (pintype "passive"))
    )
    (net (code "59") (name "unconnected-(U1A-P1_CLKP-PadE11)") (class "Default")
      (node (ref "U1") (pin "E11") (pinfunction "P1_CLKP_E11") (pintype "passive"))
    )
    (net (code "60") (name "unconnected-(U1A-P1_DATA2N-PadD10)") (class "Default")
      (node (ref "U1") (pin "D10") (pinfunction "P1_DATA2N_D10") (pintype "passive"))
    )
    (net (code "61") (name "unconnected-(U1A-P1_DATA2P-PadD11)") (class "Default")
      (node (ref "U1") (pin "D11") (pinfunction "P1_DATA2P_D11") (pintype "passive"))
    )
    (net (code "62") (name "unconnected-(U1A-P1_DATA3N-PadF10)") (class "Default")
      (node (ref "U1") (pin "F10") (pinfunction "P1_DATA3N_F10") (pintype "passive"))
    )
    (net (code "63") (name "unconnected-(U1A-P1_DATA3P-PadF11)") (class "Default")
      (node (ref "U1") (pin "F11") (pinfunction "P1_DATA3P_F11") (pintype "passive"))
    )
    (net (code "64") (name "unconnected-(U1A-P1_DATA4N-PadG10)") (class "Default")
      (node (ref "U1") (pin "G10") (pinfunction "P1_DATA4N_G10") (pintype "passive"))
    )
    (net (code "65") (name "unconnected-(U1A-P1_DATA4P-PadG11)") (class "Default")
      (node (ref "U1") (pin "G11") (pinfunction "P1_DATA4P_G11") (pintype "passive"))
    )
    (net (code "66") (name "unconnected-(U1A-P1_DATAN-PadC10)") (class "Default")
      (node (ref "U1") (pin "C10") (pinfunction "P1_DATAN_C10") (pintype "passive"))
    )
    (net (code "67") (name "unconnected-(U1A-P1_DATAP-PadC11)") (class "Default")
      (node (ref "U1") (pin "C11") (pinfunction "P1_DATAP_C11") (pintype "passive"))
    )
    (net (code "68") (name "unconnected-(U1B-P1_VDD_SLVS_PHY-PadH10)") (class "Default")
      (node (ref "U1") (pin "H10") (pinfunction "P1_VDD_SLVS_PHY_H10") (pintype "passive"))
    )
    (net (code "69") (name "unconnected-(U1B-VDD_SLVS_PHY-PadA3)") (class "Default")
      (node (ref "U1") (pin "A3") (pinfunction "VDD_SLVS_PHY_A3") (pintype "passive"))
    )
    (net (code "70") (name "unconnected-(U2A-ATEST1-PadJ8)") (class "Default")
      (node (ref "U2") (pin "J8") (pinfunction "ATEST1_J8") (pintype "passive"))
    )
    (net (code "71") (name "unconnected-(U2A-ATEST2-PadC1)") (class "Default")
      (node (ref "U2") (pin "C1") (pinfunction "ATEST2_C1") (pintype "passive"))
    )
    (net (code "72") (name "unconnected-(U2A-DATA3N-PadB5)") (class "Default")
      (node (ref "U2") (pin "B5") (pinfunction "DATA3N_B5") (pintype "passive"))
    )
    (net (code "73") (name "unconnected-(U2A-DATA3P-PadA5)") (class "Default")
      (node (ref "U2") (pin "A5") (pinfunction "DATA3P_A5") (pintype "passive"))
    )
    (net (code "74") (name "unconnected-(U2A-DATA4N-PadB4)") (class "Default")
      (node (ref "U2") (pin "B4") (pinfunction "DATA4N_B4") (pintype "passive"))
    )
    (net (code "75") (name "unconnected-(U2A-DATA4P-PadA4)") (class "Default")
      (node (ref "U2") (pin "A4") (pinfunction "DATA4P_A4") (pintype "passive"))
    )
    (net (code "76") (name "unconnected-(U2A-GPI2-PadE1)") (class "Default")
      (node (ref "U2") (pin "E1") (pinfunction "GPI2_E1") (pintype "passive"))
    )
    (net (code "77") (name "unconnected-(U2A-GPI3-PadE2)") (class "Default")
      (node (ref "U2") (pin "E2") (pinfunction "GPI3_E2") (pintype "passive"))
    )
    (net (code "78") (name "unconnected-(U2A-GPIO1-PadD2)") (class "Default")
      (node (ref "U2") (pin "D2") (pinfunction "GPIO1_D2") (pintype "passive"))
    )
    (net (code "79") (name "unconnected-(U2A-P1_CLKN-PadE10)") (class "Default")
      (node (ref "U2") (pin "E10") (pinfunction "P1_CLKN_E10") (pintype "passive"))
    )
    (net (code "80") (name "unconnected-(U2A-P1_CLKP-PadE11)") (class "Default")
      (node (ref "U2") (pin "E11") (pinfunction "P1_CLKP_E11") (pintype "passive"))
    )
    (net (code "81") (name "unconnected-(U2A-P1_DATA2N-PadD10)") (class "Default")
      (node (ref "U2") (pin "D10") (pinfunction "P1_DATA2N_D10") (pintype "passive"))
    )
    (net (code "82") (name "unconnected-(U2A-P1_DATA2P-PadD11)") (class "Default")
      (node (ref "U2") (pin "D11") (pinfunction "P1_DATA2P_D11") (pintype "passive"))
    )
    (net (code "83") (name "unconnected-(U2A-P1_DATA3N-PadF10)") (class "Default")
      (node (ref "U2") (pin "F10") (pinfunction "P1_DATA3N_F10") (pintype "passive"))
    )
    (net (code "84") (name "unconnected-(U2A-P1_DATA3P-PadF11)") (class "Default")
      (node (ref "U2") (pin "F11") (pinfunction "P1_DATA3P_F11") (pintype "passive"))
    )
    (net (code "85") (name "unconnected-(U2A-P1_DATA4N-PadG10)") (class "Default")
      (node (ref "U2") (pin "G10") (pinfunction "P1_DATA4N_G10") (pintype "passive"))
    )
    (net (code "86") (name "unconnected-(U2A-P1_DATA4P-PadG11)") (class "Default")
      (node (ref "U2") (pin "G11") (pinfunction "P1_DATA4P_G11") (pintype "passive"))
    )
    (net (code "87") (name "unconnected-(U2A-P1_DATAN-PadC10)") (class "Default")
      (node (ref "U2") (pin "C10") (pinfunction "P1_DATAN_C10") (pintype "passive"))
    )
    (net (code "88") (name "unconnected-(U2A-P1_DATAP-PadC11)") (class "Default")
      (node (ref "U2") (pin "C11") (pinfunction "P1_DATAP_C11") (pintype "passive"))
    )
    (net (code "89") (name "unconnected-(U2B-P1_VDD_SLVS_PHY-PadH10)") (class "Default")
      (node (ref "U2") (pin "H10") (pinfunction "P1_VDD_SLVS_PHY_H10") (pintype "passive"))
    )
    (net (code "90") (name "unconnected-(U2B-VDD_SLVS_PHY-PadA3)") (class "Default")
      (node (ref "U2") (pin "A3") (pinfunction "VDD_SLVS_PHY_A3") (pintype "passive"))
    )
    (net (code "91") (name "unconnected-(U3A-ATEST1-PadJ8)") (class "Default")
      (node (ref "U3") (pin "J8") (pinfunction "ATEST1_J8") (pintype "passive"))
    )
    (net (code "92") (name "unconnected-(U3A-ATEST2-PadC1)") (class "Default")
      (node (ref "U3") (pin "C1") (pinfunction "ATEST2_C1") (pintype "passive"))
    )
    (net (code "93") (name "unconnected-(U3A-DATA3N-PadB5)") (class "Default")
      (node (ref "U3") (pin "B5") (pinfunction "DATA3N_B5") (pintype "passive"))
    )
    (net (code "94") (name "unconnected-(U3A-DATA3P-PadA5)") (class "Default")
      (node (ref "U3") (pin "A5") (pinfunction "DATA3P_A5") (pintype "passive"))
    )
    (net (code "95") (name "unconnected-(U3A-DATA4N-PadB4)") (class "Default")
      (node (ref "U3") (pin "B4") (pinfunction "DATA4N_B4") (pintype "passive"))
    )
    (net (code "96") (name "unconnected-(U3A-DATA4P-PadA4)") (class "Default")
      (node (ref "U3") (pin "A4") (pinfunction "DATA4P_A4") (pintype "passive"))
    )
    (net (code "97") (name "unconnected-(U3A-GPI2-PadE1)") (class "Default")
      (node (ref "U3") (pin "E1") (pinfunction "GPI2_E1") (pintype "passive"))
    )
    (net (code "98") (name "unconnected-(U3A-GPI3-PadE2)") (class "Default")
      (node (ref "U3") (pin "E2") (pinfunction "GPI3_E2") (pintype "passive"))
    )
    (net (code "99") (name "unconnected-(U3A-GPIO1-PadD2)") (class "Default")
      (node (ref "U3") (pin "D2") (pinfunction "GPIO1_D2") (pintype "passive"))
    )
    (net (code "100") (name "unconnected-(U3A-P1_CLKN-PadE10)") (class "Default")
      (node (ref "U3") (pin "E10") (pinfunction "P1_CLKN_E10") (pintype "passive"))
    )
    (net (code "101") (name "unconnected-(U3A-P1_CLKP-PadE11)") (class "Default")
      (node (ref "U3") (pin "E11") (pinfunction "P1_CLKP_E11") (pintype "passive"))
    )
    (net (code "102") (name "unconnected-(U3A-P1_DATA2N-PadD10)") (class "Default")
      (node (ref "U3") (pin "D10") (pinfunction "P1_DATA2N_D10") (pintype "passive"))
    )
    (net (code "103") (name "unconnected-(U3A-P1_DATA2P-PadD11)") (class "Default")
      (node (ref "U3") (pin "D11") (pinfunction "P1_DATA2P_D11") (pintype "passive"))
    )
    (net (code "104") (name "unconnected-(U3A-P1_DATA3N-PadF10)") (class "Default")
      (node (ref "U3") (pin "F10") (pinfunction "P1_DATA3N_F10") (pintype "passive"))
    )
    (net (code "105") (name "unconnected-(U3A-P1_DATA3P-PadF11)") (class "Default")
      (node (ref "U3") (pin "F11") (pinfunction "P1_DATA3P_F11") (pintype "passive"))
    )
    (net (code "106") (name "unconnected-(U3A-P1_DATA4N-PadG10)") (class "Default")
      (node (ref "U3") (pin "G10") (pinfunction "P1_DATA4N_G10") (pintype "passive"))
    )
    (net (code "107") (name "unconnected-(U3A-P1_DATA4P-PadG11)") (class "Default")
      (node (ref "U3") (pin "G11") (pinfunction "P1_DATA4P_G11") (pintype "passive"))
    )
    (net (code "108") (name "unconnected-(U3A-P1_DATAN-PadC10)") (class "Default")
      (node (ref "U3") (pin "C10") (pinfunction "P1_DATAN_C10") (pintype "passive"))
    )
    (net (code "109") (name "unconnected-(U3A-P1_DATAP-PadC11)") (class "Default")
      (node (ref "U3") (pin "C11") (pinfunction "P1_DATAP_C11") (pintype "passive"))
    )
    (net (code "110") (name "unconnected-(U3B-P1_VDD_SLVS_PHY-PadH10)") (class "Default")
      (node (ref "U3") (pin "H10") (pinfunction "P1_VDD_SLVS_PHY_H10") (pintype "passive"))
    )
    (net (code "111") (name "unconnected-(U3B-VDD_SLVS_PHY-PadA3)") (class "Default")
      (node (ref "U3") (pin "A3") (pinfunction "VDD_SLVS_PHY_A3") (pintype "passive"))
    )
    (net (code "112") (name "unconnected-(U4A-ATEST1-PadJ8)") (class "Default")
      (node (ref "U4") (pin "J8") (pinfunction "ATEST1_J8") (pintype "passive"))
    )
    (net (code "113") (name "unconnected-(U4A-ATEST2-PadC1)") (class "Default")
      (node (ref "U4") (pin "C1") (pinfunction "ATEST2_C1") (pintype "passive"))
    )
    (net (code "114") (name "unconnected-(U4A-DATA3N-PadB5)") (class "Default")
      (node (ref "U4") (pin "B5") (pinfunction "DATA3N_B5") (pintype "passive"))
    )
    (net (code "115") (name "unconnected-(U4A-DATA3P-PadA5)") (class "Default")
      (node (ref "U4") (pin "A5") (pinfunction "DATA3P_A5") (pintype "passive"))
    )
    (net (code "116") (name "unconnected-(U4A-DATA4N-PadB4)") (class "Default")
      (node (ref "U4") (pin "B4") (pinfunction "DATA4N_B4") (pintype "passive"))
    )
    (net (code "117") (name "unconnected-(U4A-DATA4P-PadA4)") (class "Default")
      (node (ref "U4") (pin "A4") (pinfunction "DATA4P_A4") (pintype "passive"))
    )
    (net (code "118") (name "unconnected-(U4A-GPI2-PadE1)") (class "Default")
      (node (ref "U4") (pin "E1") (pinfunction "GPI2_E1") (pintype "passive"))
    )
    (net (code "119") (name "unconnected-(U4A-GPI3-PadE2)") (class "Default")
      (node (ref "U4") (pin "E2") (pinfunction "GPI3_E2") (pintype "passive"))
    )
    (net (code "120") (name "unconnected-(U4A-GPIO1-PadD2)") (class "Default")
      (node (ref "U4") (pin "D2") (pinfunction "GPIO1_D2") (pintype "passive"))
    )
    (net (code "121") (name "unconnected-(U4A-P1_CLKN-PadE10)") (class "Default")
      (node (ref "U4") (pin "E10") (pinfunction "P1_CLKN_E10") (pintype "passive"))
    )
    (net (code "122") (name "unconnected-(U4A-P1_CLKP-PadE11)") (class "Default")
      (node (ref "U4") (pin "E11") (pinfunction "P1_CLKP_E11") (pintype "passive"))
    )
    (net (code "123") (name "unconnected-(U4A-P1_DATA2N-PadD10)") (class "Default")
      (node (ref "U4") (pin "D10") (pinfunction "P1_DATA2N_D10") (pintype "passive"))
    )
    (net (code "124") (name "unconnected-(U4A-P1_DATA2P-PadD11)") (class "Default")
      (node (ref "U4") (pin "D11") (pinfunction "P1_DATA2P_D11") (pintype "passive"))
    )
    (net (code "125") (name "unconnected-(U4A-P1_DATA3N-PadF10)") (class "Default")
      (node (ref "U4") (pin "F10") (pinfunction "P1_DATA3N_F10") (pintype "passive"))
    )
    (net (code "126") (name "unconnected-(U4A-P1_DATA3P-PadF11)") (class "Default")
      (node (ref "U4") (pin "F11") (pinfunction "P1_DATA3P_F11") (pintype "passive"))
    )
    (net (code "127") (name "unconnected-(U4A-P1_DATA4N-PadG10)") (class "Default")
      (node (ref "U4") (pin "G10") (pinfunction "P1_DATA4N_G10") (pintype "passive"))
    )
    (net (code "128") (name "unconnected-(U4A-P1_DATA4P-PadG11)") (class "Default")
      (node (ref "U4") (pin "G11") (pinfunction "P1_DATA4P_G11") (pintype "passive"))
    )
    (net (code "129") (name "unconnected-(U4A-P1_DATAN-PadC10)") (class "Default")
      (node (ref "U4") (pin "C10") (pinfunction "P1_DATAN_C10") (pintype "passive"))
    )
    (net (code "130") (name "unconnected-(U4A-P1_DATAP-PadC11)") (class "Default")
      (node (ref "U4") (pin "C11") (pinfunction "P1_DATAP_C11") (pintype "passive"))
    )
    (net (code "131") (name "unconnected-(U4B-P1_VDD_SLVS_PHY-PadH10)") (class "Default")
      (node (ref "U4") (pin "H10") (pinfunction "P1_VDD_SLVS_PHY_H10") (pintype "passive"))
    )
    (net (code "132") (name "unconnected-(U4B-VDD_SLVS_PHY-PadA3)") (class "Default")
      (node (ref "U4") (pin "A3") (pinfunction "VDD_SLVS_PHY_A3") (pintype "passive"))
    )
  )
)
